# Sheet1.net
KiCad netlist of a schematic drawn in Altium Designer
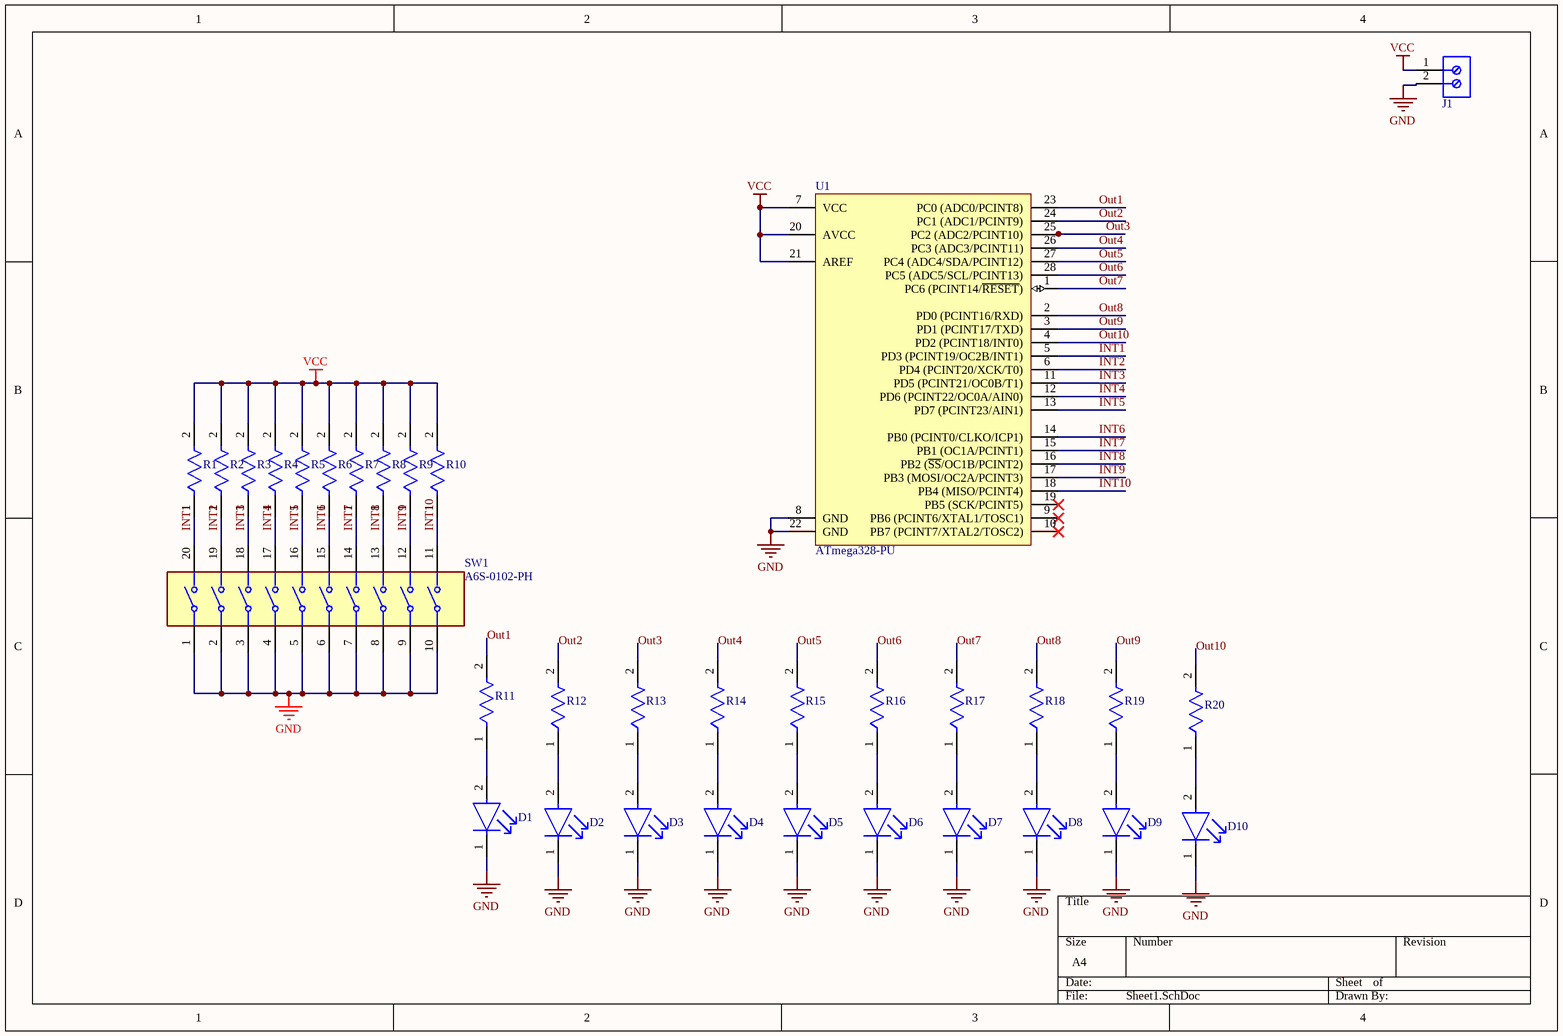
[diagram p0: Sheet1.SchDoc]

(export (version "E")
  (design (tool "Eeschema 10.0.6"))
  (components
    (comp (ref "D1")
      (value "LTST-C230KRKT")
      (footprint "FP-LTST-C230KRKT-MFG")
      (description "LED RED CLEAR CHIP SMD")
      (libsource (lib "Ejemplo2") (part "CMP-22017-000041-1"))
    )
    (comp (ref "D2")
      (value "LTST-C230KRKT")
      (footprint "FP-LTST-C230KRKT-MFG")
      (description "LED RED CLEAR CHIP SMD")
      (libsource (lib "Ejemplo2") (part "CMP-22017-000041-1"))
    )
    (comp (ref "D3")
      (value "LTST-C230KRKT")
      (footprint "FP-LTST-C230KRKT-MFG")
      (description "LED RED CLEAR CHIP SMD")
      (libsource (lib "Ejemplo2") (part "CMP-22017-000041-1"))
    )
    (comp (ref "D4")
      (value "LTST-C230KRKT")
      (footprint "FP-LTST-C230KRKT-MFG")
      (description "LED RED CLEAR CHIP SMD")
      (libsource (lib "Ejemplo2") (part "CMP-22017-000041-1"))
    )
    (comp (ref "D5")
      (value "LTST-C230KRKT")
      (footprint "FP-LTST-C230KRKT-MFG")
      (description "LED RED CLEAR CHIP SMD")
      (libsource (lib "Ejemplo2") (part "CMP-22017-000041-1"))
    )
    (comp (ref "D6")
      (value "LTST-C230KRKT")
      (footprint "FP-LTST-C230KRKT-MFG")
      (description "LED RED CLEAR CHIP SMD")
      (libsource (lib "Ejemplo2") (part "CMP-22017-000041-1"))
    )
    (comp (ref "D7")
      (value "LTST-C230KRKT")
      (footprint "FP-LTST-C230KRKT-MFG")
      (description "LED RED CLEAR CHIP SMD")
      (libsource (lib "Ejemplo2") (part "CMP-22017-000041-1"))
    )
    (comp (ref "D8")
      (value "LTST-C230KRKT")
      (footprint "FP-LTST-C230KRKT-MFG")
      (description "LED RED CLEAR CHIP SMD")
      (libsource (lib "Ejemplo2") (part "CMP-22017-000041-1"))
    )
    (comp (ref "D9")
      (value "LTST-C230KRKT")
      (footprint "FP-LTST-C230KRKT-MFG")
      (description "LED RED CLEAR CHIP SMD")
      (libsource (lib "Ejemplo2") (part "CMP-22017-000041-1"))
    )
    (comp (ref "D10")
      (value "LTST-C230KRKT")
      (footprint "FP-LTST-C230KRKT-MFG")
      (description "LED RED CLEAR CHIP SMD")
      (libsource (lib "Ejemplo2") (part "CMP-22017-000041-1"))
    )
    (comp (ref "J1")
      (value "691214110002")
      (footprint "691214110002")
      (description "Serie 2141 - 3.50 mm Horizontal Entry Modular with Rising Cage Clamp WR-TBL, 2 pin")
      (fields (field (name "MANUFACTURER") "Wurth Elektronik") (field (name "PUBLISHER") "WurthElektronik"))
      (libsource (lib "Ejemplo2") (part "CMP-1502-02464-1"))
    )
    (comp (ref "R1")
      (value "RT0805BRD07249RL")
      (footprint "FP-RT0805-MFG")
      (description "RES SMD 249 OHM 0.1% 1/8W 0805")
      (fields
        (field (name "OCTOPART") "https://octopart.com/rt0805brd07249rl-yageo-1410573")
        (field (name "MANUFACTURER") "Yageo")
      )
      (libsource (lib "Ejemplo2") (part "CMP-03412-035801-1"))
    )
    (comp (ref "R2")
      (value "RT0805BRD07249RL")
      (footprint "FP-RT0805-MFG")
      (description "RES SMD 249 OHM 0.1% 1/8W 0805")
      (fields
        (field (name "OCTOPART") "https://octopart.com/rt0805brd07249rl-yageo-1410573")
        (field (name "MANUFACTURER") "Yageo")
      )
      (libsource (lib "Ejemplo2") (part "CMP-03412-035801-1"))
    )
    (comp (ref "R3")
      (value "RT0805BRD07249RL")
      (footprint "FP-RT0805-MFG")
      (description "RES SMD 249 OHM 0.1% 1/8W 0805")
      (fields
        (field (name "OCTOPART") "https://octopart.com/rt0805brd07249rl-yageo-1410573")
        (field (name "MANUFACTURER") "Yageo")
      )
      (libsource (lib "Ejemplo2") (part "CMP-03412-035801-1"))
    )
    (comp (ref "R4")
      (value "RT0805BRD07249RL")
      (footprint "FP-RT0805-MFG")
      (description "RES SMD 249 OHM 0.1% 1/8W 0805")
      (fields
        (field (name "OCTOPART") "https://octopart.com/rt0805brd07249rl-yageo-1410573")
        (field (name "MANUFACTURER") "Yageo")
      )
      (libsource (lib "Ejemplo2") (part "CMP-03412-035801-1"))
    )
    (comp (ref "R5")
      (value "RT0805BRD07249RL")
      (footprint "FP-RT0805-MFG")
      (description "RES SMD 249 OHM 0.1% 1/8W 0805")
      (fields
        (field (name "OCTOPART") "https://octopart.com/rt0805brd07249rl-yageo-1410573")
        (field (name "MANUFACTURER") "Yageo")
      )
      (libsource (lib "Ejemplo2") (part "CMP-03412-035801-1"))
    )
    (comp (ref "R6")
      (value "RT0805BRD07249RL")
      (footprint "FP-RT0805-MFG")
      (description "RES SMD 249 OHM 0.1% 1/8W 0805")
      (fields
        (field (name "OCTOPART") "https://octopart.com/rt0805brd07249rl-yageo-1410573")
        (field (name "MANUFACTURER") "Yageo")
      )
      (libsource (lib "Ejemplo2") (part "CMP-03412-035801-1"))
    )
    (comp (ref "R7")
      (value "RT0805BRD07249RL")
      (footprint "FP-RT0805-MFG")
      (description "RES SMD 249 OHM 0.1% 1/8W 0805")
      (fields
        (field (name "OCTOPART") "https://octopart.com/rt0805brd07249rl-yageo-1410573")
        (field (name "MANUFACTURER") "Yageo")
      )
      (libsource (lib "Ejemplo2") (part "CMP-03412-035801-1"))
    )
    (comp (ref "R8")
      (value "RT0805BRD07249RL")
      (footprint "FP-RT0805-MFG")
      (description "RES SMD 249 OHM 0.1% 1/8W 0805")
      (fields
        (field (name "OCTOPART") "https://octopart.com/rt0805brd07249rl-yageo-1410573")
        (field (name "MANUFACTURER") "Yageo")
      )
      (libsource (lib "Ejemplo2") (part "CMP-03412-035801-1"))
    )
    (comp (ref "R9")
      (value "RT0805BRD07249RL")
      (footprint "FP-RT0805-MFG")
      (description "RES SMD 249 OHM 0.1% 1/8W 0805")
      (fields
        (field (name "OCTOPART") "https://octopart.com/rt0805brd07249rl-yageo-1410573")
        (field (name "MANUFACTURER") "Yageo")
      )
      (libsource (lib "Ejemplo2") (part "CMP-03412-035801-1"))
    )
    (comp (ref "R10")
      (value "RT0805BRD07249RL")
      (footprint "FP-RT0805-MFG")
      (description "RES SMD 249 OHM 0.1% 1/8W 0805")
      (fields
        (field (name "OCTOPART") "https://octopart.com/rt0805brd07249rl-yageo-1410573")
        (field (name "MANUFACTURER") "Yageo")
      )
      (libsource (lib "Ejemplo2") (part "CMP-03412-035801-1"))
    )
    (comp (ref "R11")
      (value "RT0805BRD07249RL")
      (footprint "FP-RT0805-MFG")
      (description "RES SMD 249 OHM 0.1% 1/8W 0805")
      (fields
        (field (name "OCTOPART") "https://octopart.com/rt0805brd07249rl-yageo-1410573")
        (field (name "MANUFACTURER") "Yageo")
      )
      (libsource (lib "Ejemplo2") (part "CMP-03412-035801-1"))
    )
    (comp (ref "R12")
      (value "RT0805BRD07249RL")
      (footprint "FP-RT0805-MFG")
      (description "RES SMD 249 OHM 0.1% 1/8W 0805")
      (fields
        (field (name "OCTOPART") "https://octopart.com/rt0805brd07249rl-yageo-1410573")
        (field (name "MANUFACTURER") "Yageo")
      )
      (libsource (lib "Ejemplo2") (part "CMP-03412-035801-1"))
    )
    (comp (ref "R13")
      (value "RT0805BRD07249RL")
      (footprint "FP-RT0805-MFG")
      (description "RES SMD 249 OHM 0.1% 1/8W 0805")
      (fields
        (field (name "OCTOPART") "https://octopart.com/rt0805brd07249rl-yageo-1410573")
        (field (name "MANUFACTURER") "Yageo")
      )
      (libsource (lib "Ejemplo2") (part "CMP-03412-035801-1"))
    )
    (comp (ref "R14")
      (value "RT0805BRD07249RL")
      (footprint "FP-RT0805-MFG")
      (description "RES SMD 249 OHM 0.1% 1/8W 0805")
      (fields
        (field (name "OCTOPART") "https://octopart.com/rt0805brd07249rl-yageo-1410573")
        (field (name "MANUFACTURER") "Yageo")
      )
      (libsource (lib "Ejemplo2") (part "CMP-03412-035801-1"))
    )
    (comp (ref "R15")
      (value "RT0805BRD07249RL")
      (footprint "FP-RT0805-MFG")
      (description "RES SMD 249 OHM 0.1% 1/8W 0805")
      (fields
        (field (name "OCTOPART") "https://octopart.com/rt0805brd07249rl-yageo-1410573")
        (field (name "MANUFACTURER") "Yageo")
      )
      (libsource (lib "Ejemplo2") (part "CMP-03412-035801-1"))
    )
    (comp (ref "R16")
      (value "RT0805BRD07249RL")
      (footprint "FP-RT0805-MFG")
      (description "RES SMD 249 OHM 0.1% 1/8W 0805")
      (fields
        (field (name "OCTOPART") "https://octopart.com/rt0805brd07249rl-yageo-1410573")
        (field (name "MANUFACTURER") "Yageo")
      )
      (libsource (lib "Ejemplo2") (part "CMP-03412-035801-1"))
    )
    (comp (ref "R17")
      (value "RT0805BRD07249RL")
      (footprint "FP-RT0805-MFG")
      (description "RES SMD 249 OHM 0.1% 1/8W 0805")
      (fields
        (field (name "OCTOPART") "https://octopart.com/rt0805brd07249rl-yageo-1410573")
        (field (name "MANUFACTURER") "Yageo")
      )
      (libsource (lib "Ejemplo2") (part "CMP-03412-035801-1"))
    )
    (comp (ref "R18")
      (value "RT0805BRD07249RL")
      (footprint "FP-RT0805-MFG")
      (description "RES SMD 249 OHM 0.1% 1/8W 0805")
      (fields
        (field (name "OCTOPART") "https://octopart.com/rt0805brd07249rl-yageo-1410573")
        (field (name "MANUFACTURER") "Yageo")
      )
      (libsource (lib "Ejemplo2") (part "CMP-03412-035801-1"))
    )
    (comp (ref "R19")
      (value "RT0805BRD07249RL")
      (footprint "FP-RT0805-MFG")
      (description "RES SMD 249 OHM 0.1% 1/8W 0805")
      (fields
        (field (name "OCTOPART") "https://octopart.com/rt0805brd07249rl-yageo-1410573")
        (field (name "MANUFACTURER") "Yageo")
      )
      (libsource (lib "Ejemplo2") (part "CMP-03412-035801-1"))
    )
    (comp (ref "R20")
      (value "RT0805BRD07249RL")
      (footprint "FP-RT0805-MFG")
      (description "RES SMD 249 OHM 0.1% 1/8W 0805")
      (fields
        (field (name "OCTOPART") "https://octopart.com/rt0805brd07249rl-yageo-1410573")
        (field (name "MANUFACTURER") "Yageo")
      )
      (libsource (lib "Ejemplo2") (part "CMP-03412-035801-1"))
    )
    (comp (ref "SW1")
      (value "A6S-0102-PH")
      (footprint "FP-A6S-0102-PH-MFG")
      (description "SWITCH SLIDE DIP SPST 25MA 24V")
      (libsource (lib "Ejemplo2") (part "CMP-08827-000074-1"))
    )
    (comp (ref "U1")
      (value "ATmega328-PU")
      (footprint "28P3")
      (libsource (lib "Ejemplo2") (part "CMP-0095-00015-2"))
    )
  )
  (nets
    (net (code "1") (name "/INT1") (class "Default")
      (node (ref "R1") (pin "1") (pinfunction "1_1") (pintype "passive"))
      (node (ref "SW1") (pin "20") (pinfunction "20_20") (pintype "passive"))
      (node (ref "U1") (pin "5") (pinfunction "PD3_(PCINT19/OC2B/INT1)_5") (pintype "passive"))
    )
    (net (code "2") (name "/INT2") (class "Default")
      (node (ref "R2") (pin "1") (pinfunction "1_1") (pintype "passive"))
      (node (ref "SW1") (pin "19") (pinfunction "19_19") (pintype "passive"))
      (node (ref "U1") (pin "6") (pinfunction "PD4_(PCINT20/XCK/T0)_6") (pintype "passive"))
    )
    (net (code "3") (name "/INT3") (class "Default")
      (node (ref "R3") (pin "1") (pinfunction "1_1") (pintype "passive"))
      (node (ref "SW1") (pin "18") (pinfunction "18_18") (pintype "passive"))
      (node (ref "U1") (pin "11") (pinfunction "PD5_(PCINT21/OC0B/T1)_11") (pintype "passive"))
    )
    (net (code "4") (name "/INT4") (class "Default")
      (node (ref "R4") (pin "1") (pinfunction "1_1") (pintype "passive"))
      (node (ref "SW1") (pin "17") (pinfunction "17_17") (pintype "passive"))
      (node (ref "U1") (pin "12") (pinfunction "PD6_(PCINT22/OC0A/AIN0)_12") (pintype "passive"))
    )
    (net (code "5") (name "/INT5") (class "Default")
      (node (ref "R5") (pin "1") (pinfunction "1_1") (pintype "passive"))
      (node (ref "SW1") (pin "16") (pinfunction "16_16") (pintype "passive"))
      (node (ref "U1") (pin "13") (pinfunction "PD7_(PCINT23/AIN1)_13") (pintype "passive"))
    )
    (net (code "6") (name "/INT6") (class "Default")
      (node (ref "R6") (pin "1") (pinfunction "1_1") (pintype "passive"))
      (node (ref "SW1") (pin "15") (pinfunction "15_15") (pintype "passive"))
      (node (ref "U1") (pin "14") (pinfunction "PB0_(PCINT0/CLKO/ICP1)_14") (pintype "passive"))
    )
    (net (code "7") (name "/INT7") (class "Default")
      (node (ref "R7") (pin "1") (pinfunction "1_1") (pintype "passive"))
      (node (ref "SW1") (pin "14") (pinfunction "14_14") (pintype "passive"))
      (node (ref "U1") (pin "15") (pinfunction "PB1_(OC1A/PCINT1)_15") (pintype "passive"))
    )
    (net (code "8") (name "/INT8") (class "Default")
      (node (ref "R8") (pin "1") (pinfunction "1_1") (pintype "passive"))
      (node (ref "SW1") (pin "13") (pinfunction "13_13") (pintype "passive"))
      (node (ref "U1") (pin "16") (pinfunction "PB2_(~{SS}/OC1B/PCINT2)_16") (pintype "passive"))
    )
    (net (code "9") (name "/INT9") (class "Default")
      (node (ref "R9") (pin "1") (pinfunction "1_1") (pintype "passive"))
      (node (ref "SW1") (pin "12") (pinfunction "12_12") (pintype "passive"))
      (node (ref "U1") (pin "17") (pinfunction "PB3_(MOSI/OC2A/PCINT3)_17") (pintype "passive"))
    )
    (net (code "10") (name "/INT10") (class "Default")
      (node (ref "R10") (pin "1") (pinfunction "1_1") (pintype "passive"))
      (node (ref "SW1") (pin "11") (pinfunction "11_11") (pintype "passive"))
      (node (ref "U1") (pin "18") (pinfunction "PB4_(MISO/PCINT4)_18") (pintype "passive"))
    )
    (net (code "11") (name "/Out1") (class "Default")
      (node (ref "R11") (pin "2") (pinfunction "2_2") (pintype "passive"))
      (node (ref "U1") (pin "23") (pinfunction "PC0_(ADC0/PCINT8)_23") (pintype "passive"))
    )
    (net (code "12") (name "/Out2") (class "Default")
      (node (ref "R12") (pin "2") (pinfunction "2_2") (pintype "passive"))
      (node (ref "U1") (pin "24") (pinfunction "PC1_(ADC1/PCINT9)_24") (pintype "passive"))
    )
    (net (code "13") (name "/Out3") (class "Default")
      (node (ref "R13") (pin "2") (pinfunction "2_2") (pintype "passive"))
      (node (ref "U1") (pin "25") (pinfunction "PC2_(ADC2/PCINT10)_25") (pintype "passive"))
    )
    (net (code "14") (name "/Out4") (class "Default")
      (node (ref "R14") (pin "2") (pinfunction "2_2") (pintype "passive"))
      (node (ref "U1") (pin "26") (pinfunction "PC3_(ADC3/PCINT11)_26") (pintype "passive"))
    )
    (net (code "15") (name "/Out5") (class "Default")
      (node (ref "R15") (pin "2") (pinfunction "2_2") (pintype "passive"))
      (node (ref "U1") (pin "27") (pinfunction "PC4_(ADC4/SDA/PCINT12)_27") (pintype "passive"))
    )
    (net (code "16") (name "/Out6") (class "Default")
      (node (ref "R16") (pin "2") (pinfunction "2_2") (pintype "passive"))
      (node (ref "U1") (pin "28") (pinfunction "PC5_(ADC5/SCL/PCINT13)_28") (pintype "passive"))
    )
    (net (code "17") (name "/Out7") (class "Default")
      (node (ref "R17") (pin "2") (pinfunction "2_2") (pintype "passive"))
      (node (ref "U1") (pin "1") (pinfunction "PC6_(PCINT14/~{RESET})_1") (pintype "bidirectional"))
    )
    (net (code "18") (name "/Out8") (class "Default")
      (node (ref "R18") (pin "2") (pinfunction "2_2") (pintype "passive"))
      (node (ref "U1") (pin "2") (pinfunction "PD0_(PCINT16/RXD)_2") (pintype "passive"))
    )
    (net (code "19") (name "/Out9") (class "Default")
      (node (ref "R19") (pin "2") (pinfunction "2_2") (pintype "passive"))
      (node (ref "U1") (pin "3") (pinfunction "PD1_(PCINT17/TXD)_3") (pintype "passive"))
    )
    (net (code "20") (name "/Out10") (class "Default")
      (node (ref "R20") (pin "2") (pinfunction "2_2") (pintype "passive"))
      (node (ref "U1") (pin "4") (pinfunction "PD2_(PCINT18/INT0)_4") (pintype "passive"))
    )
    (net (code "21") (name "GND") (class "Default")
      (node (ref "D1") (pin "1") (pinfunction "C_1") (pintype "passive"))
      (node (ref "D10") (pin "1") (pinfunction "C_1") (pintype "passive"))
      (node (ref "D2") (pin "1") (pinfunction "C_1") (pintype "passive"))
      (node (ref "D3") (pin "1") (pinfunction "C_1") (pintype "passive"))
      (node (ref "D4") (pin "1") (pinfunction "C_1") (pintype "passive"))
      (node (ref "D5") (pin "1") (pinfunction "C_1") (pintype "passive"))
      (node (ref "D6") (pin "1") (pinfunction "C_1") (pintype "passive"))
      (node (ref "D7") (pin "1") (pinfunction "C_1") (pintype "passive"))
      (node (ref "D8") (pin "1") (pinfunction "C_1") (pintype "passive"))
      (node (ref "D9") (pin "1") (pinfunction "C_1") (pintype "passive"))
      (node (ref "J1") (pin "2") (pinfunction "2_2") (pintype "passive"))
      (node (ref "SW1") (pin "1") (pinfunction "1_1") (pintype "passive"))
      (node (ref "SW1") (pin "10") (pinfunction "10_10") (pintype "passive"))
      (node (ref "SW1") (pin "2") (pinfunction "2_2") (pintype "passive"))
      (node (ref "SW1") (pin "3") (pinfunction "3_3") (pintype "passive"))
      (node (ref "SW1") (pin "4") (pinfunction "4_4") (pintype "passive"))
      (node (ref "SW1") (pin "5") (pinfunction "5_5") (pintype "passive"))
      (node (ref "SW1") (pin "6") (pinfunction "6_6") (pintype "passive"))
      (node (ref "SW1") (pin "7") (pinfunction "7_7") (pintype "passive"))
      (node (ref "SW1") (pin "8") (pinfunction "8_8") (pintype "passive"))
      (node (ref "SW1") (pin "9") (pinfunction "9_9") (pintype "passive"))
      (node (ref "U1") (pin "22") (pinfunction "GND_22") (pintype "power_in"))
      (node (ref "U1") (pin "8") (pinfunction "GND_8") (pintype "power_in"))
    )
    (net (code "22") (name "Net-(D1-A)") (class "Default")
      (node (ref "D1") (pin "2") (pinfunction "A_2") (pintype "passive"))
      (node (ref "R11") (pin "1") (pinfunction "1_1") (pintype "passive"))
    )
    (net (code "23") (name "Net-(D2-A)") (class "Default")
      (node (ref "D2") (pin "2") (pinfunction "A_2") (pintype "passive"))
      (node (ref "R12") (pin "1") (pinfunction "1_1") (pintype "passive"))
    )
    (net (code "24") (name "Net-(D3-A)") (class "Default")
      (node (ref "D3") (pin "2") (pinfunction "A_2") (pintype "passive"))
      (node (ref "R13") (pin "1") (pinfunction "1_1") (pintype "passive"))
    )
    (net (code "25") (name "Net-(D4-A)") (class "Default")
      (node (ref "D4") (pin "2") (pinfunction "A_2") (pintype "passive"))
      (node (ref "R14") (pin "1") (pinfunction "1_1") (pintype "passive"))
    )
    (net (code "26") (name "Net-(D5-A)") (class "Default")
      (node (ref "D5") (pin "2") (pinfunction "A_2") (pintype "passive"))
      (node (ref "R15") (pin "1") (pinfunction "1_1") (pintype "passive"))
    )
    (net (code "27") (name "Net-(D6-A)") (class "Default")
      (node (ref "D6") (pin "2") (pinfunction "A_2") (pintype "passive"))
      (node (ref "R16") (pin "1") (pinfunction "1_1") (pintype "passive"))
    )
    (net (code "28") (name "Net-(D7-A)") (class "Default")
      (node (ref "D7") (pin "2") (pinfunction "A_2") (pintype "passive"))
      (node (ref "R17") (pin "1") (pinfunction "1_1") (pintype "passive"))
    )
    (net (code "29") (name "Net-(D8-A)") (class "Default")
      (node (ref "D8") (pin "2") (pinfunction "A_2") (pintype "passive"))
      (node (ref "R18") (pin "1") (pinfunction "1_1") (pintype "passive"))
    )
    (net (code "30") (name "Net-(D9-A)") (class "Default")
      (node (ref "D9") (pin "2") (pinfunction "A_2") (pintype "passive"))
      (node (ref "R19") (pin "1") (pinfunction "1_1") (pintype "passive"))
    )
    (net (code "31") (name "Net-(D10-A)") (class "Default")
      (node (ref "D10") (pin "2") (pinfunction "A_2") (pintype "passive"))
      (node (ref "R20") (pin "1") (pinfunction "1_1") (pintype "passive"))
    )
    (net (code "32") (name "VCC") (class "Default")
      (node (ref "J1") (pin "1") (pinfunction "1_1") (pintype "passive"))
      (node (ref "R1") (pin "2") (pinfunction "2_2") (pintype "passive"))
      (node (ref "R10") (pin "2") (pinfunction "2_2") (pintype "passive"))
      (node (ref "R2") (pin "2") (pinfunction "2_2") (pintype "passive"))
      (node (ref "R3") (pin "2") (pinfunction "2_2") (pintype "passive"))
      (node (ref "R4") (pin "2") (pinfunction "2_2") (pintype "passive"))
      (node (ref "R5") (pin "2") (pinfunction "2_2") (pintype "passive"))
      (node (ref "R6") (pin "2") (pinfunction "2_2") (pintype "passive"))
      (node (ref "R7") (pin "2") (pinfunction "2_2") (pintype "passive"))
      (node (ref "R8") (pin "2") (pinfunction "2_2") (pintype "passive"))
      (node (ref "R9") (pin "2") (pinfunction "2_2") (pintype "passive"))
      (node (ref "U1") (pin "20") (pinfunction "AVCC_20") (pintype "power_in"))
      (node (ref "U1") (pin "21") (pinfunction "AREF_21") (pintype "power_in"))
      (node (ref "U1") (pin "7") (pinfunction "VCC_7") (pintype "power_in"))
    )
    (net (code "33") (name "unconnected-(U1-PB5_(SCK{slash}PCINT5)-Pad19)") (class "Default")
      (node (ref "U1") (pin "19") (pinfunction "PB5_(SCK/PCINT5)_19") (pintype "passive+no_connect"))
    )
    (net (code "34") (name "unconnected-(U1-PB6_(PCINT6{slash}XTAL1{slash}TOSC1)-Pad9)") (class "Default")
      (node (ref "U1") (pin "9") (pinfunction "PB6_(PCINT6/XTAL1/TOSC1)_9") (pintype "passive+no_connect"))
    )
    (net (code "35") (name "unconnected-(U1-PB7_(PCINT7{slash}XTAL2{slash}TOSC2)-Pad10)") (class "Default")
      (node (ref "U1") (pin "10") (pinfunction "PB7_(PCINT7/XTAL2/TOSC2)_10") (pintype "passive+no_connect"))
    )
  )
)
